# 1-Schematic_Antenna_Mini-Whip_TH.net
KiCad netlist of a schematic drawn in EasyEDA
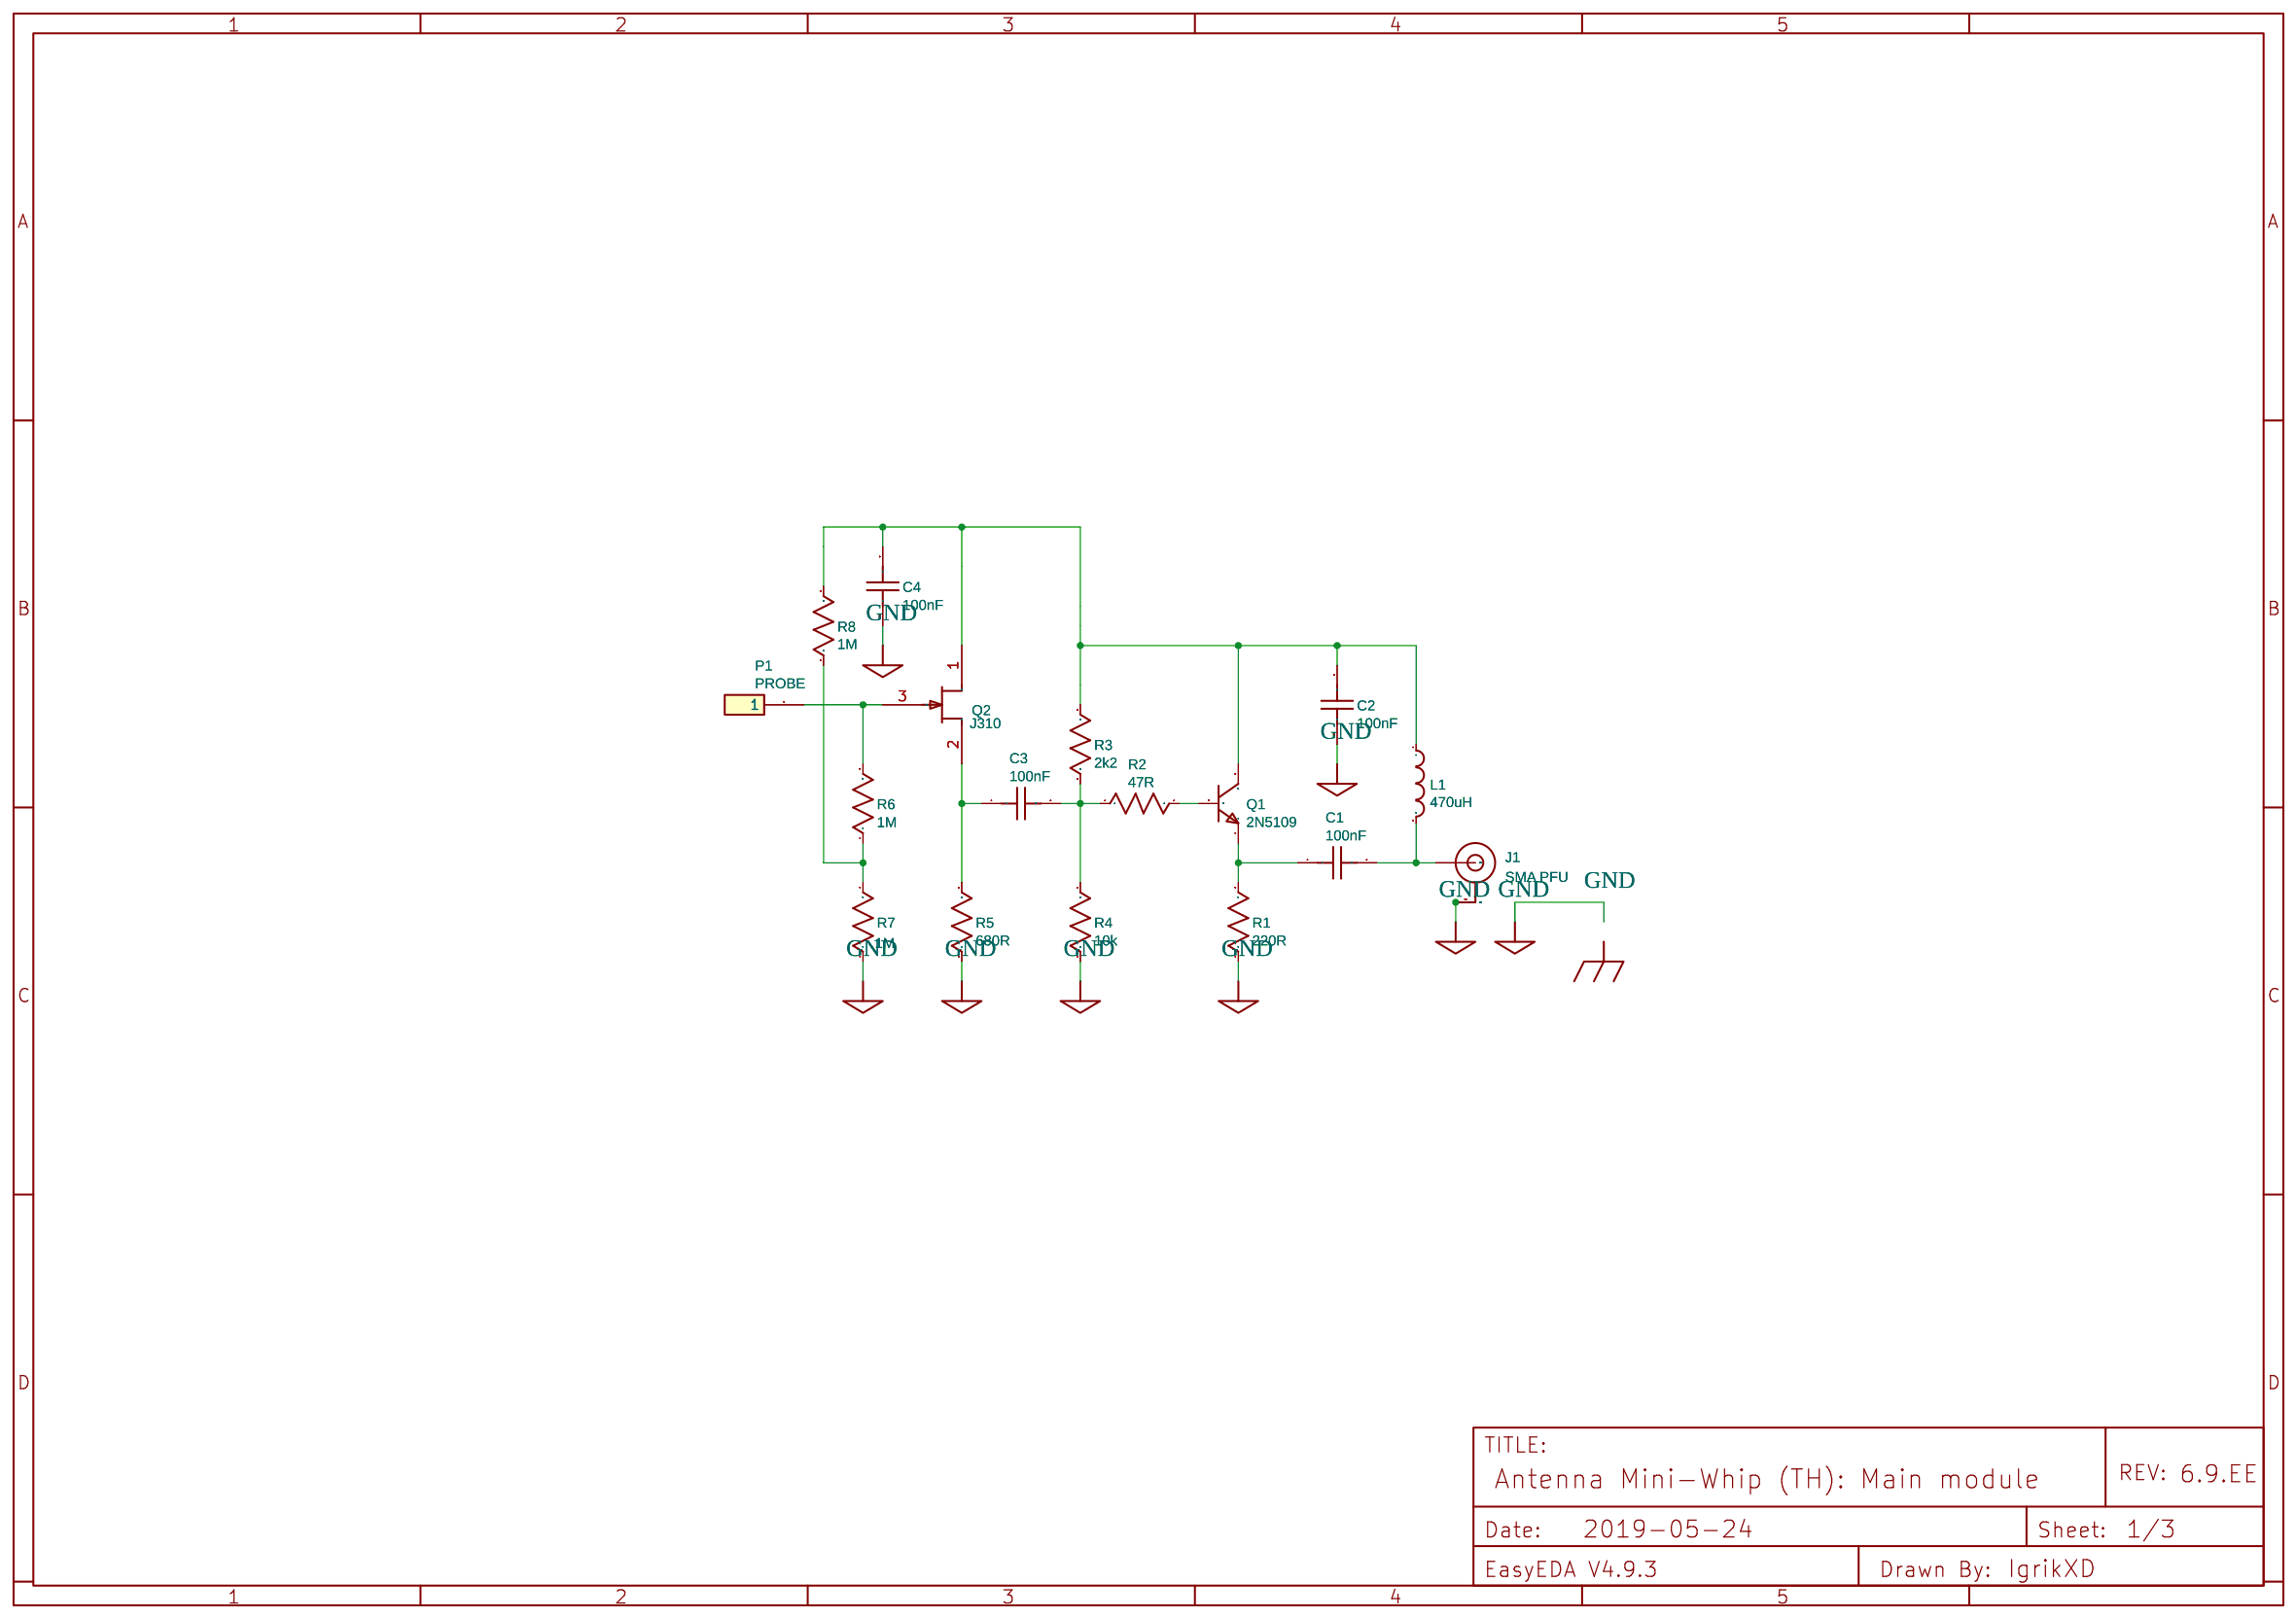
[diagram p0: Antenna Mini-Whip (TH): Main module]
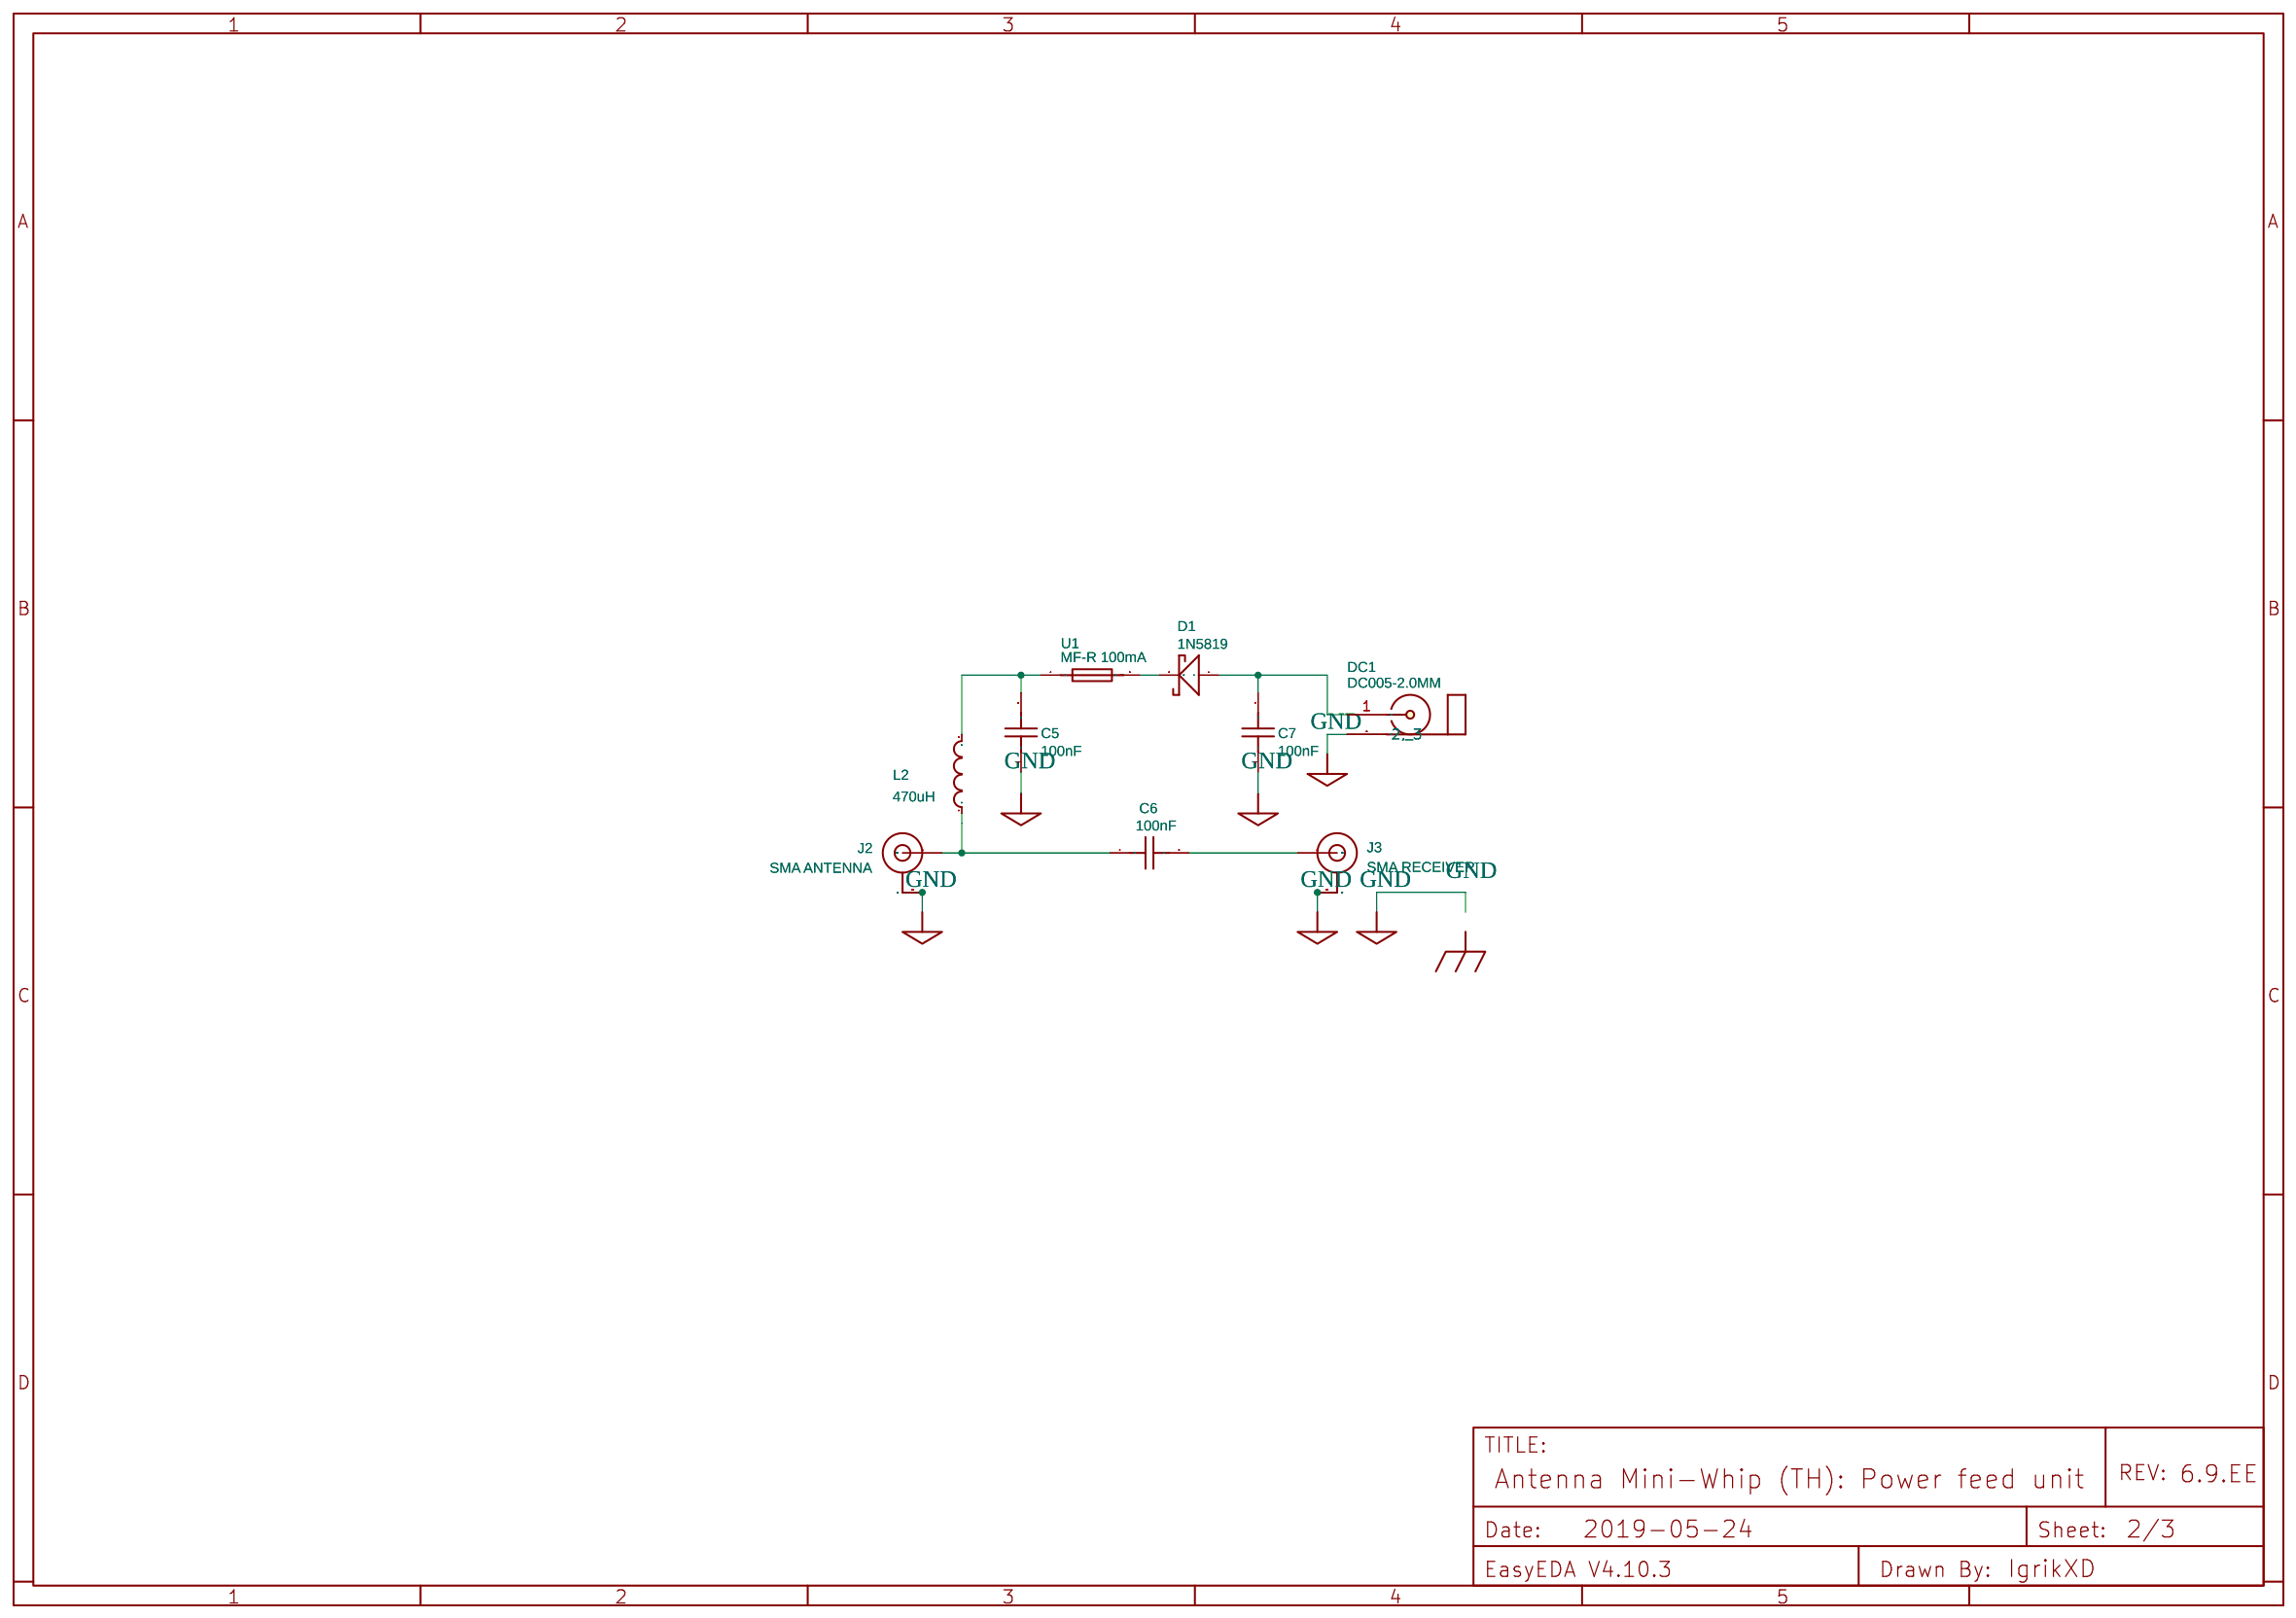
[diagram p1: Antenna Mini-Whip (TH): Power feed unit]
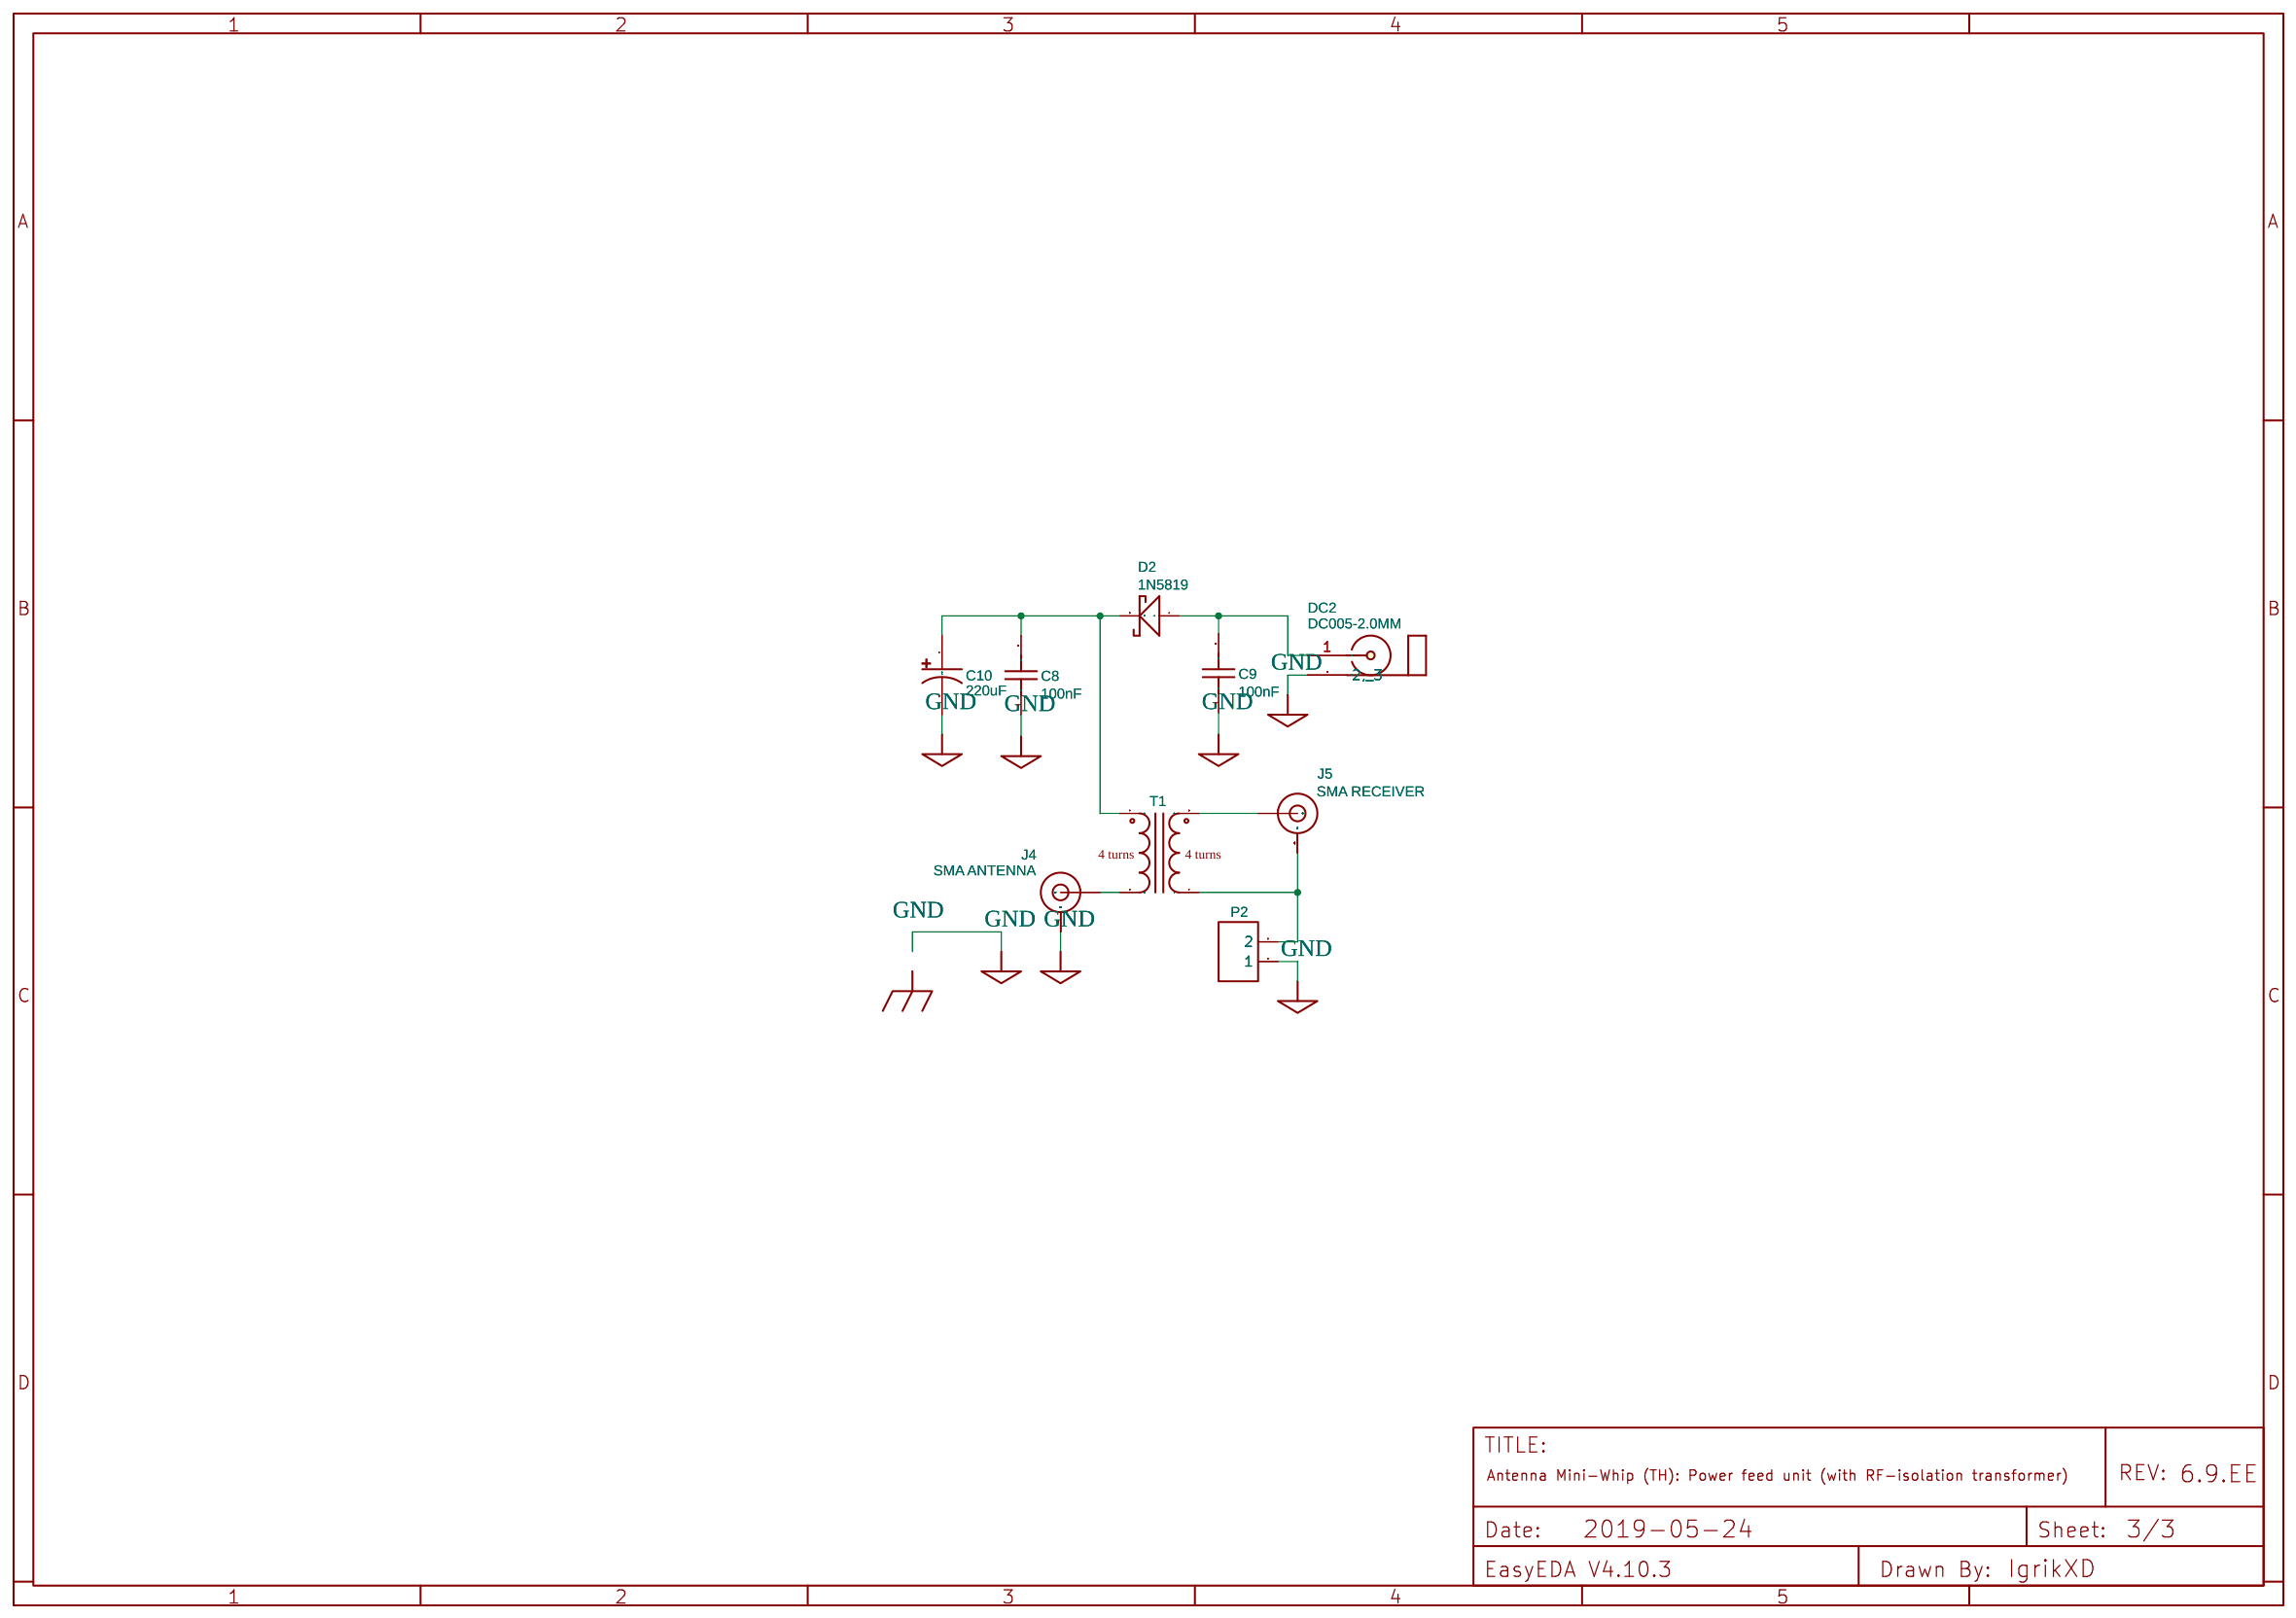
[diagram p2: Antenna Mini-Whip (TH): Power feed unit (with RF-isolation transformer)]

(export (version "E")
  (design (tool "Eeschema 10.0.6"))
  (components
    (comp (ref "C1")
      (value "100nF")
      (fields
        (field (name "BOM_Manufacturer Part") "Monolithic0805B104J500F3")
        (field (name "BOM_Supplier Part") "C110282")
      )
      (libsource (lib "") (part "Capacitor_1"))
    )
    (comp (ref "C2")
      (value "100nF")
      (fields
        (field (name "BOM_Manufacturer Part") "Monolithic0805B104J500F3")
        (field (name "BOM_Supplier Part") "C110282")
      )
      (libsource (lib "") (part "Capacitor"))
    )
    (comp (ref "C3")
      (value "100nF")
      (fields
        (field (name "BOM_Manufacturer Part") "Monolithic0805B104J500F3")
        (field (name "BOM_Supplier Part") "C110282")
      )
      (libsource (lib "") (part "Capacitor_1"))
    )
    (comp (ref "C4")
      (value "100nF")
      (fields
        (field (name "BOM_Manufacturer Part") "Monolithic0805B104J500F3")
        (field (name "BOM_Supplier Part") "C110282")
      )
      (libsource (lib "") (part "Capacitor"))
    )
    (comp (ref "J1")
      (value "SMA PFU")
      (fields
        (field (name "BOM_Manufacturer Part") "ANKX01.0093")
        (field (name "BOM_Supplier Part") "C129604")
      )
      (libsource (lib "") (part "Unknown_740_430"))
    )
    (comp (ref "L1")
      (value "470uH")
      (fields
        (field (name "BOM_Manufacturer Part") "LGA0510-471KP52E")
        (field (name "BOM_Supplier Part") "C72362")
      )
      (libsource (lib "") (part "Inductor"))
    )
    (comp (ref "P1")
      (value "PROBE")
      (fields
        (field (name "BOM_Manufacturer Part") "Header-Male-2.54_1x1")
        (field (name "BOM_Supplier Part") "C81276")
      )
      (libsource (lib "") (part "Unknown_385_350"))
    )
    (comp (ref "Q1")
      (value "2N5109")
      (fields (field (name "BOM_Supplier Part") "2N5109CS-ND"))
      (libsource (lib "") (part "Unknown_610_400"))
    )
    (comp (ref "Q2")
      (value "J310")
      (fields (field (name "BOM_Supplier Part") "J310-ND"))
      (libsource (lib "") (part "Unknown_470_350"))
    )
    (comp (ref "R1")
      (value "220R")
      (fields
        (field (name "BOM_Manufacturer Part") "MFR0S2F2200A20")
        (field (name "BOM_Supplier Part") "C58583")
      )
      (libsource (lib "") (part "Resistor"))
    )
    (comp (ref "R2")
      (value "47R")
      (fields
        (field (name "BOM_Manufacturer Part") "MF1/4W-47Ω±1% T52")
        (field (name "BOM_Supplier Part") "C119296")
      )
      (libsource (lib "") (part "Resistor_1"))
    )
    (comp (ref "R3")
      (value "2k2")
      (fields
        (field (name "BOM_Manufacturer Part") "MFR0W4F2201A50")
        (field (name "BOM_Supplier Part") "C58595")
      )
      (libsource (lib "") (part "Resistor"))
    )
    (comp (ref "R4")
      (value "10k")
      (fields
        (field (name "BOM_Manufacturer Part") "MFR0W4F1002A50")
        (field (name "BOM_Supplier Part") "C57436")
      )
      (libsource (lib "") (part "Resistor"))
    )
    (comp (ref "R5")
      (value "680R")
      (fields
        (field (name "BOM_Manufacturer Part") "MFR0W4F6800A50")
        (field (name "BOM_Supplier Part") "C58599")
      )
      (libsource (lib "") (part "Resistor"))
    )
    (comp (ref "R6")
      (value "1M")
      (fields
        (field (name "BOM_Manufacturer Part") "MFR0W4F1004A50")
        (field (name "BOM_Supplier Part") "C58596")
      )
      (libsource (lib "") (part "Resistor"))
    )
    (comp (ref "R7")
      (value "1M")
      (fields
        (field (name "BOM_Manufacturer Part") "MFR0W4F1004A50")
        (field (name "BOM_Supplier Part") "C58596")
      )
      (libsource (lib "") (part "Resistor"))
    )
    (comp (ref "R8")
      (value "1M")
      (fields
        (field (name "BOM_Manufacturer Part") "MFR0W4F1004A50")
        (field (name "BOM_Supplier Part") "C58596")
      )
      (libsource (lib "") (part "Resistor"))
    )
    (comp (ref "C5")
      (value "100nF")
      (fields
        (field (name "BOM_Manufacturer Part") "Monolithic0805B104J500F3")
        (field (name "BOM_Supplier Part") "C110282")
      )
      (libsource (lib "") (part "Capacitor"))
    )
    (comp (ref "C6")
      (value "100nF")
      (fields
        (field (name "BOM_Manufacturer Part") "Monolithic0805B104J500F3")
        (field (name "BOM_Supplier Part") "C110282")
      )
      (libsource (lib "") (part "Capacitor_1"))
    )
    (comp (ref "C7")
      (value "100nF")
      (fields
        (field (name "BOM_Manufacturer Part") "Monolithic0805B104J500F3")
        (field (name "BOM_Supplier Part") "C110282")
      )
      (libsource (lib "") (part "Capacitor"))
    )
    (comp (ref "D1")
      (value "1N5819")
      (fields (field (name "BOM_Supplier Part") "C2474"))
      (libsource (lib "") (part "Unknown_595_335"))
    )
    (comp (ref "DC1")
      (value "DC005-2.0MM")
      (fields
        (field (name "BOM_Manufacturer Part") "DC-005 5.5-2.0")
        (field (name "BOM_Supplier Part") "C16214")
      )
      (libsource (lib "") (part "Unknown_695_355"))
    )
    (comp (ref "J2")
      (value "SMA ANTENNA")
      (fields
        (field (name "BOM_Manufacturer Part") "ANKX01.0093")
        (field (name "BOM_Supplier Part") "C129604")
      )
      (libsource (lib "") (part "Unknown_450_425"))
    )
    (comp (ref "J3")
      (value "SMA RECEIVER")
      (fields
        (field (name "BOM_Manufacturer Part") "ANKX01.0093")
        (field (name "BOM_Supplier Part") "C129604")
      )
      (libsource (lib "") (part "Unknown_670_425"))
    )
    (comp (ref "L2")
      (value "470uH")
      (fields
        (field (name "BOM_Manufacturer Part") "LGA0510-471KP52E")
        (field (name "BOM_Supplier Part") "C72362")
      )
      (libsource (lib "") (part "Inductor"))
    )
    (comp (ref "U1")
      (value "MF-R 100mA")
      (fields (field (name "BOM_Manufacturer Part") "MF-R010") (field (name "BOM_Supplier Part") "C89660"))
      (libsource (lib "") (part "Unknown_540_335"))
    )
    (comp (ref "C8")
      (value "100nF")
      (fields
        (field (name "BOM_Manufacturer Part") "Monolithic0805B104J500F3")
        (field (name "BOM_Supplier Part") "C110282")
      )
      (libsource (lib "") (part "Capacitor"))
    )
    (comp (ref "C9")
      (value "100nF")
      (fields
        (field (name "BOM_Manufacturer Part") "Monolithic0805B104J500F3")
        (field (name "BOM_Supplier Part") "C110282")
      )
      (libsource (lib "") (part "Capacitor"))
    )
    (comp (ref "C10")
      (value "220uF")
      (fields (field (name "BOM_Manufacturer Part") "NULL") (field (name "BOM_Supplier Part") "C43838"))
      (libsource (lib "") (part "Cap_Electrolytic(TH)_D6.3XF2.5_US"))
    )
    (comp (ref "D2")
      (value "1N5819")
      (fields (field (name "BOM_Supplier Part") "C2474"))
      (libsource (lib "") (part "Unknown_575_305"))
    )
    (comp (ref "DC2")
      (value "DC005-2.0MM")
      (fields
        (field (name "BOM_Manufacturer Part") "DC-005 5.5-2.0")
        (field (name "BOM_Supplier Part") "C16214")
      )
      (libsource (lib "") (part "Unknown_675_325"))
    )
    (comp (ref "J4")
      (value "SMA ANTENNA")
      (fields
        (field (name "BOM_Manufacturer Part") "ANKX01.0093")
        (field (name "BOM_Supplier Part") "C129604")
      )
      (libsource (lib "") (part "Unknown_535_465"))
    )
    (comp (ref "J5")
      (value "SMA RECEIVER")
      (fields
        (field (name "BOM_Manufacturer Part") "ANKX01.0093")
        (field (name "BOM_Supplier Part") "C129604")
      )
      (libsource (lib "") (part "Unknown_645_425"))
    )
    (comp (ref "P2")
      (value "Header-Female-2.54_1x2")
      (fields (field (name "BOM_Manufacturer Part") "826629-2") (field (name "BOM_Supplier Part") "C86471"))
      (libsource (lib "") (part "Unknown_625_475"))
    )
    (comp (ref "T1")
      (value "XFMR")
      (fields (field (name "BOM_Manufacturer Part") "NULL"))
      (libsource (lib "") (part "TRANSFORMER_US"))
    )
  )
  (nets
    (net (code "1") (name "GND") (class "Default")
      (node (ref "C10") (pin "2") (pinfunction "2_2") (pintype "unspecified"))
      (node (ref "C2") (pin "1") (pinfunction "1_1") (pintype "unspecified"))
      (node (ref "C4") (pin "1") (pinfunction "1_1") (pintype "unspecified"))
      (node (ref "C5") (pin "1") (pinfunction "1_1") (pintype "unspecified"))
      (node (ref "C7") (pin "1") (pinfunction "1_1") (pintype "unspecified"))
      (node (ref "C8") (pin "1") (pinfunction "1_1") (pintype "unspecified"))
      (node (ref "C9") (pin "1") (pinfunction "1_1") (pintype "unspecified"))
      (node (ref "DC1") (pin "2") (pinfunction "2,_3_2") (pintype "input"))
      (node (ref "DC1") (pin "3") (pinfunction "3_3") (pintype "input"))
      (node (ref "DC2") (pin "2") (pinfunction "2,_3_2") (pintype "input"))
      (node (ref "DC2") (pin "3") (pinfunction "3_3") (pintype "input"))
      (node (ref "J1") (pin "GND@0") (pinfunction "GND_GND@0") (pintype "unspecified"))
      (node (ref "J1") (pin "GND@1") (pinfunction "GND_GND@1") (pintype "unspecified"))
      (node (ref "J1") (pin "GND@2") (pinfunction "GND_GND@2") (pintype "unspecified"))
      (node (ref "J1") (pin "GND@3") (pinfunction "GND_GND@3") (pintype "unspecified"))
      (node (ref "J2") (pin "GND@0") (pinfunction "GND_GND@0") (pintype "unspecified"))
      (node (ref "J2") (pin "GND@1") (pinfunction "GND_GND@1") (pintype "unspecified"))
      (node (ref "J2") (pin "GND@2") (pinfunction "GND_GND@2") (pintype "unspecified"))
      (node (ref "J2") (pin "GND@3") (pinfunction "GND_GND@3") (pintype "unspecified"))
      (node (ref "J3") (pin "GND@0") (pinfunction "GND_GND@0") (pintype "unspecified"))
      (node (ref "J3") (pin "GND@1") (pinfunction "GND_GND@1") (pintype "unspecified"))
      (node (ref "J3") (pin "GND@2") (pinfunction "GND_GND@2") (pintype "unspecified"))
      (node (ref "J3") (pin "GND@3") (pinfunction "GND_GND@3") (pintype "unspecified"))
      (node (ref "J4") (pin "GND@0") (pinfunction "GND_GND@0") (pintype "unspecified"))
      (node (ref "J4") (pin "GND@1") (pinfunction "GND_GND@1") (pintype "unspecified"))
      (node (ref "J4") (pin "GND@2") (pinfunction "GND_GND@2") (pintype "unspecified"))
      (node (ref "J4") (pin "GND@3") (pinfunction "GND_GND@3") (pintype "unspecified"))
      (node (ref "P2") (pin "1") (pinfunction "1_1") (pintype "input"))
      (node (ref "R1") (pin "1") (pinfunction "1_1") (pintype "unspecified"))
      (node (ref "R4") (pin "1") (pinfunction "1_1") (pintype "unspecified"))
      (node (ref "R5") (pin "1") (pinfunction "1_1") (pintype "unspecified"))
      (node (ref "R7") (pin "1") (pinfunction "1_1") (pintype "unspecified"))
    )
    (net (code "2") (name "Net-(C3-Pad2)") (class "Default")
      (node (ref "C3") (pin "2") (pinfunction "2_2") (pintype "unspecified"))
      (node (ref "R2") (pin "1") (pinfunction "1_1") (pintype "unspecified"))
      (node (ref "R3") (pin "1") (pinfunction "1_1") (pintype "unspecified"))
      (node (ref "R4") (pin "2") (pinfunction "2_2") (pintype "unspecified"))
    )
    (net (code "3") (name "Net-(C5-Pad2)") (class "Default")
      (node (ref "C5") (pin "2") (pinfunction "2_2") (pintype "unspecified"))
      (node (ref "L2") (pin "2") (pinfunction "2_2") (pintype "unspecified"))
      (node (ref "U1") (pin "1") (pinfunction "1_1") (pintype "unspecified"))
    )
    (net (code "4") (name "Net-(C10-Pad1)") (class "Default")
      (node (ref "C10") (pin "1") (pinfunction "1_1") (pintype "unspecified"))
      (node (ref "C8") (pin "2") (pinfunction "2_2") (pintype "unspecified"))
      (node (ref "D2") (pin "C") (pinfunction "C_C") (pintype "unspecified"))
      (node (ref "T1") (pin "1") (pinfunction "1_1") (pintype "unspecified"))
    )
    (net (code "5") (name "Net-(D1-PadC)") (class "Default")
      (node (ref "D1") (pin "C") (pinfunction "C_C") (pintype "unspecified"))
      (node (ref "U1") (pin "2") (pinfunction "2_2") (pintype "unspecified"))
    )
    (net (code "6") (name "Net-(DC1-VCC)") (class "Default")
      (node (ref "C7") (pin "2") (pinfunction "2_2") (pintype "unspecified"))
      (node (ref "D1") (pin "A") (pinfunction "A_A") (pintype "unspecified"))
      (node (ref "DC1") (pin "1") (pinfunction "VCC_1") (pintype "input"))
    )
    (net (code "7") (name "Net-(DC2-VCC)") (class "Default")
      (node (ref "C9") (pin "2") (pinfunction "2_2") (pintype "unspecified"))
      (node (ref "D2") (pin "A") (pinfunction "A_A") (pintype "unspecified"))
      (node (ref "DC2") (pin "1") (pinfunction "VCC_1") (pintype "input"))
    )
    (net (code "8") (name "Net-(J1-SIGNAL)") (class "Default")
      (node (ref "C1") (pin "2") (pinfunction "2_2") (pintype "unspecified"))
      (node (ref "J1") (pin "SIG") (pinfunction "SIGNAL_SIG") (pintype "unspecified"))
      (node (ref "L1") (pin "2") (pinfunction "2_2") (pintype "unspecified"))
    )
    (net (code "9") (name "Net-(J2-SIGNAL)") (class "Default")
      (node (ref "C6") (pin "1") (pinfunction "1_1") (pintype "unspecified"))
      (node (ref "J2") (pin "SIG") (pinfunction "SIGNAL_SIG") (pintype "unspecified"))
      (node (ref "L2") (pin "1") (pinfunction "1_1") (pintype "unspecified"))
    )
    (net (code "10") (name "Net-(J3-SIGNAL)") (class "Default")
      (node (ref "C6") (pin "2") (pinfunction "2_2") (pintype "unspecified"))
      (node (ref "J3") (pin "SIG") (pinfunction "SIGNAL_SIG") (pintype "unspecified"))
    )
    (net (code "11") (name "Net-(J4-SIGNAL)") (class "Default")
      (node (ref "J4") (pin "SIG") (pinfunction "SIGNAL_SIG") (pintype "unspecified"))
      (node (ref "T1") (pin "2") (pinfunction "2_2") (pintype "unspecified"))
    )
    (net (code "12") (name "Net-(J5-GND-PadGND@0)") (class "Default")
      (node (ref "J5") (pin "GND@0") (pinfunction "GND_GND@0") (pintype "unspecified"))
      (node (ref "J5") (pin "GND@1") (pinfunction "GND_GND@1") (pintype "unspecified"))
      (node (ref "J5") (pin "GND@2") (pinfunction "GND_GND@2") (pintype "unspecified"))
      (node (ref "J5") (pin "GND@3") (pinfunction "GND_GND@3") (pintype "unspecified"))
      (node (ref "P2") (pin "2") (pinfunction "2_2") (pintype "input"))
      (node (ref "T1") (pin "4") (pinfunction "4_4") (pintype "unspecified"))
    )
    (net (code "13") (name "Net-(J5-SIGNAL)") (class "Default")
      (node (ref "J5") (pin "SIG") (pinfunction "SIGNAL_SIG") (pintype "unspecified"))
      (node (ref "T1") (pin "3") (pinfunction "3_3") (pintype "unspecified"))
    )
    (net (code "14") (name "Net-(Q1-B)") (class "Default")
      (node (ref "Q1") (pin "2") (pinfunction "B_2") (pintype "unspecified"))
      (node (ref "R2") (pin "2") (pinfunction "2_2") (pintype "unspecified"))
    )
    (net (code "15") (name "Net-(Q1-C)") (class "Default")
      (node (ref "C2") (pin "2") (pinfunction "2_2") (pintype "unspecified"))
      (node (ref "C4") (pin "2") (pinfunction "2_2") (pintype "unspecified"))
      (node (ref "L1") (pin "1") (pinfunction "1_1") (pintype "unspecified"))
      (node (ref "Q1") (pin "3") (pinfunction "C_3") (pintype "unspecified"))
      (node (ref "Q2") (pin "1") (pinfunction "D_1") (pintype "unspecified"))
      (node (ref "R3") (pin "2") (pinfunction "2_2") (pintype "unspecified"))
      (node (ref "R8") (pin "2") (pinfunction "2_2") (pintype "unspecified"))
    )
    (net (code "16") (name "Net-(Q1-E)") (class "Default")
      (node (ref "C1") (pin "1") (pinfunction "1_1") (pintype "unspecified"))
      (node (ref "Q1") (pin "1") (pinfunction "E_1") (pintype "unspecified"))
      (node (ref "R1") (pin "2") (pinfunction "2_2") (pintype "unspecified"))
    )
    (net (code "17") (name "Net-(Q2-G)") (class "Default")
      (node (ref "P1") (pin "1") (pinfunction "1_1") (pintype "input"))
      (node (ref "Q2") (pin "3") (pinfunction "G_3") (pintype "unspecified"))
      (node (ref "R6") (pin "2") (pinfunction "2_2") (pintype "unspecified"))
    )
    (net (code "18") (name "Net-(Q2-S)") (class "Default")
      (node (ref "C3") (pin "1") (pinfunction "1_1") (pintype "unspecified"))
      (node (ref "Q2") (pin "2") (pinfunction "S_2") (pintype "unspecified"))
      (node (ref "R5") (pin "2") (pinfunction "2_2") (pintype "unspecified"))
    )
    (net (code "19") (name "Net-(R6-Pad1)") (class "Default")
      (node (ref "R6") (pin "1") (pinfunction "1_1") (pintype "unspecified"))
      (node (ref "R7") (pin "2") (pinfunction "2_2") (pintype "unspecified"))
      (node (ref "R8") (pin "1") (pinfunction "1_1") (pintype "unspecified"))
    )
  )
)
